# drive_logic.net
KiCad netlist of a schematic drawn in Altium Designer
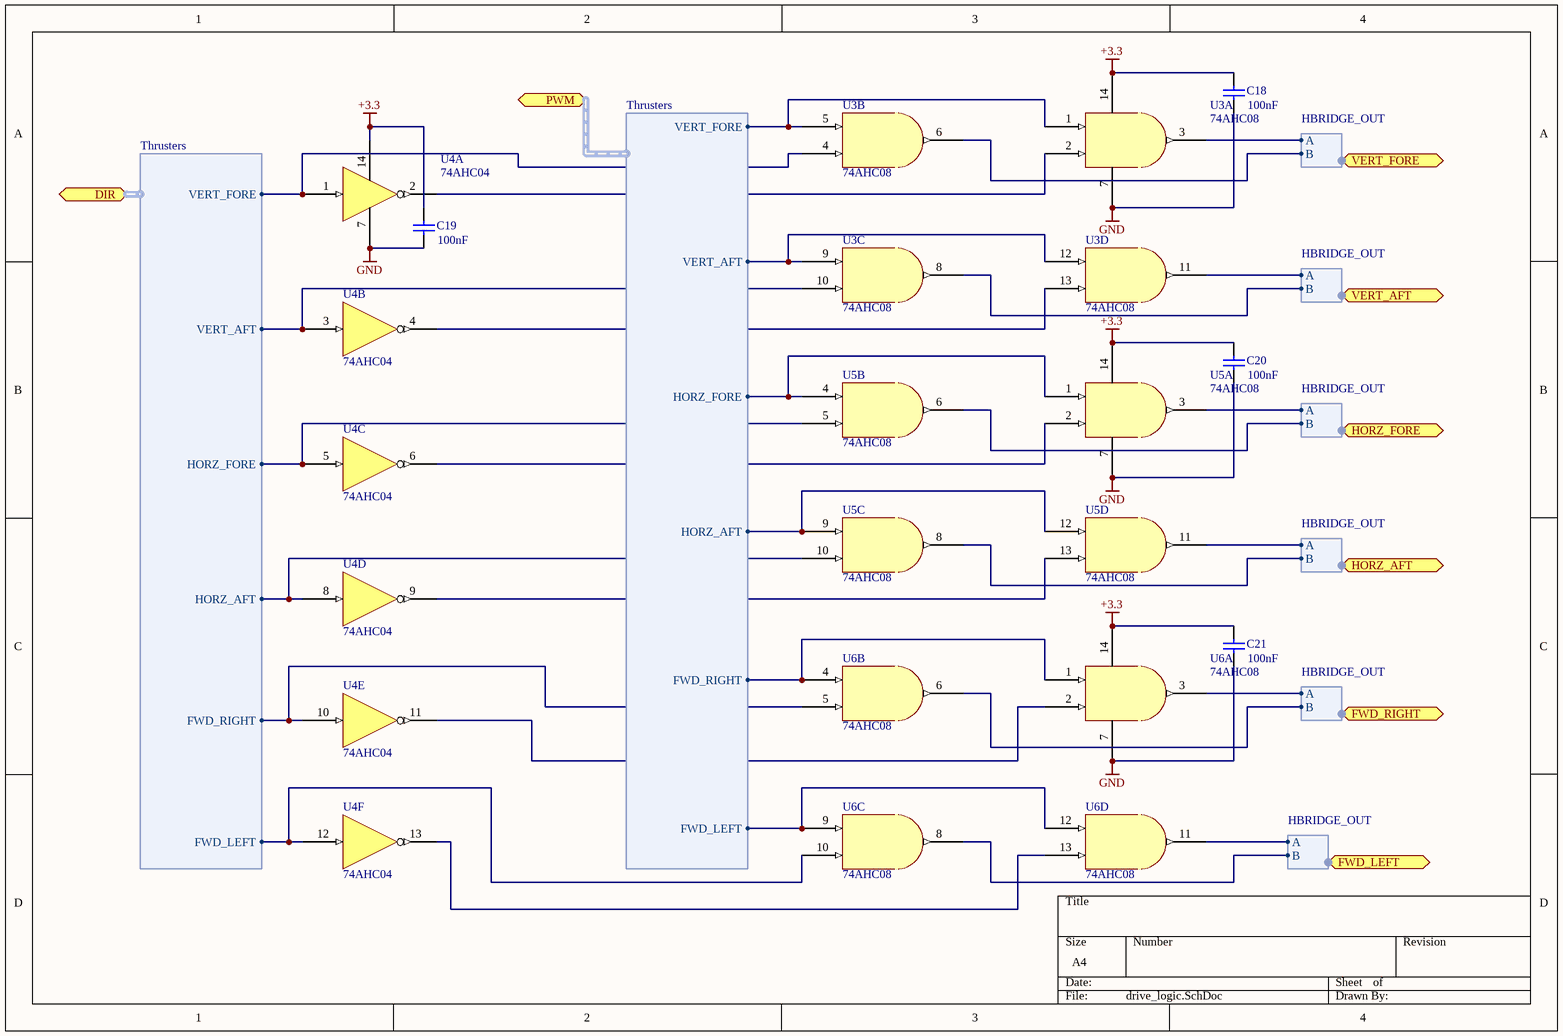
[diagram p0: drive_logic.SchDoc]

(export (version "E")
  (design (tool "Eeschema 10.0.6"))
  (components
    (comp (ref "C18")
      (value "100nF")
      (footprint "C0603")
      (description "Capacitor")
      (fields (field (name "Comment") "Cap") (field (name "PUBLISHER") "Altium Limited"))
      (libsource (lib "Miscellaneous Devices") (part "Cap"))
    )
    (comp (ref "C19")
      (value "100nF")
      (footprint "C0603")
      (description "Capacitor")
      (fields (field (name "Comment") "Cap") (field (name "PUBLISHER") "Altium Limited"))
      (libsource (lib "Miscellaneous Devices") (part "Cap"))
    )
    (comp (ref "C20")
      (value "100nF")
      (footprint "C0603")
      (description "Capacitor")
      (fields (field (name "Comment") "Cap") (field (name "PUBLISHER") "Altium Limited"))
      (libsource (lib "Miscellaneous Devices") (part "Cap"))
    )
    (comp (ref "C21")
      (value "100nF")
      (footprint "C0603")
      (description "Capacitor")
      (fields (field (name "Comment") "Cap") (field (name "PUBLISHER") "Altium Limited"))
      (libsource (lib "Miscellaneous Devices") (part "Cap"))
    )
    (comp (ref "U3")
      (value "74AHC08")
      (description "TTL Quad AND gate")
      (libsource (lib "SN74AHC08") (part "74AHC08"))
    )
    (comp (ref "U4")
      (value "74AHC04")
      (description "TTL Hex inverter")
      (libsource (lib "75ACH04") (part "74AHC04"))
    )
    (comp (ref "U5")
      (value "74AHC08")
      (description "TTL Quad AND gate")
      (libsource (lib "SN74AHC08") (part "74AHC08"))
    )
    (comp (ref "U6")
      (value "74AHC08")
      (description "TTL Quad AND gate")
      (libsource (lib "SN74AHC08") (part "74AHC08"))
    )
  )
  (nets
    (net (code "3") (name "+3.3") (class "Default")
      (node (ref "C18") (pin "2") (pinfunction "2_2") (pintype "passive"))
      (node (ref "C19") (pin "2") (pinfunction "2_2") (pintype "passive"))
      (node (ref "C20") (pin "2") (pinfunction "2_2") (pintype "passive"))
      (node (ref "C21") (pin "2") (pinfunction "2_2") (pintype "passive"))
      (node (ref "U3") (pin "14") (pintype "power_in"))
      (node (ref "U4") (pin "14") (pintype "power_in"))
      (node (ref "U5") (pin "14") (pintype "power_in"))
      (node (ref "U6") (pin "14") (pintype "power_in"))
    )
    (net (code "6") (name "GND") (class "Default")
      (node (ref "C18") (pin "1") (pinfunction "1_1") (pintype "passive"))
      (node (ref "C19") (pin "1") (pinfunction "1_1") (pintype "passive"))
      (node (ref "C20") (pin "1") (pinfunction "1_1") (pintype "passive"))
      (node (ref "C21") (pin "1") (pinfunction "1_1") (pintype "passive"))
      (node (ref "U3") (pin "7") (pintype "power_in"))
      (node (ref "U4") (pin "7") (pintype "power_in"))
      (node (ref "U5") (pin "7") (pintype "power_in"))
      (node (ref "U6") (pin "7") (pintype "power_in"))
    )
    (net (code "7") (name "Net-(U3-Pad1)") (class "Default")
      (node (ref "U3") (pin "1") (pintype "input"))
      (node (ref "U3") (pin "5") (pintype "input"))
    )
    (net (code "8") (name "Net-(U3-Pad2)") (class "Default")
      (node (ref "U3") (pin "2") (pintype "input"))
      (node (ref "U4") (pin "2") (pintype "output"))
    )
    (net (code "9") (name "Net-(U3-Pad4)") (class "Default")
      (node (ref "U3") (pin "4") (pintype "input"))
      (node (ref "U4") (pin "1") (pintype "input"))
    )
    (net (code "10") (name "Net-(U3-Pad10)") (class "Default")
      (node (ref "U3") (pin "10") (pintype "input"))
      (node (ref "U4") (pin "3") (pintype "input"))
    )
    (net (code "11") (name "Net-(U3-Pad12)") (class "Default")
      (node (ref "U3") (pin "12") (pintype "input"))
      (node (ref "U3") (pin "9") (pintype "input"))
    )
    (net (code "12") (name "Net-(U3-Pad13)") (class "Default")
      (node (ref "U3") (pin "13") (pintype "input"))
      (node (ref "U4") (pin "4") (pintype "output"))
    )
    (net (code "13") (name "Net-(U4-Pad5)") (class "Default")
      (node (ref "U4") (pin "5") (pintype "input"))
      (node (ref "U5") (pin "5") (pintype "input"))
    )
    (net (code "14") (name "Net-(U4-Pad6)") (class "Default")
      (node (ref "U4") (pin "6") (pintype "output"))
      (node (ref "U5") (pin "2") (pintype "input"))
    )
    (net (code "15") (name "Net-(U4-Pad8)") (class "Default")
      (node (ref "U4") (pin "8") (pintype "input"))
      (node (ref "U5") (pin "10") (pintype "input"))
    )
    (net (code "16") (name "Net-(U4-Pad9)") (class "Default")
      (node (ref "U4") (pin "9") (pintype "output"))
      (node (ref "U5") (pin "13") (pintype "input"))
    )
    (net (code "17") (name "Net-(U4-Pad10)") (class "Default")
      (node (ref "U4") (pin "10") (pintype "input"))
      (node (ref "U6") (pin "5") (pintype "input"))
    )
    (net (code "18") (name "Net-(U4-Pad11)") (class "Default")
      (node (ref "U4") (pin "11") (pintype "output"))
      (node (ref "U6") (pin "2") (pintype "input"))
    )
    (net (code "19") (name "Net-(U4-Pad12)") (class "Default")
      (node (ref "U4") (pin "12") (pintype "input"))
      (node (ref "U6") (pin "10") (pintype "input"))
    )
    (net (code "20") (name "Net-(U4-Pad13)") (class "Default")
      (node (ref "U4") (pin "13") (pintype "output"))
      (node (ref "U6") (pin "13") (pintype "input"))
    )
    (net (code "21") (name "Net-(U5-Pad1)") (class "Default")
      (node (ref "U5") (pin "1") (pintype "input"))
      (node (ref "U5") (pin "4") (pintype "input"))
    )
    (net (code "22") (name "Net-(U5-Pad12)") (class "Default")
      (node (ref "U5") (pin "12") (pintype "input"))
      (node (ref "U5") (pin "9") (pintype "input"))
    )
    (net (code "23") (name "Net-(U6-Pad1)") (class "Default")
      (node (ref "U6") (pin "1") (pintype "input"))
      (node (ref "U6") (pin "4") (pintype "input"))
    )
    (net (code "24") (name "Net-(U6-Pad12)") (class "Default")
      (node (ref "U6") (pin "12") (pintype "input"))
      (node (ref "U6") (pin "9") (pintype "input"))
    )
    (net (code "25") (name "unconnected-(U3-Pad3)") (class "Default")
      (node (ref "U3") (pin "3") (pintype "output"))
    )
    (net (code "26") (name "unconnected-(U3-Pad6)") (class "Default")
      (node (ref "U3") (pin "6") (pintype "output"))
    )
    (net (code "27") (name "unconnected-(U3-Pad8)") (class "Default")
      (node (ref "U3") (pin "8") (pintype "output"))
    )
    (net (code "28") (name "unconnected-(U3-Pad11)") (class "Default")
      (node (ref "U3") (pin "11") (pintype "output"))
    )
    (net (code "29") (name "unconnected-(U5-Pad3)") (class "Default")
      (node (ref "U5") (pin "3") (pintype "output"))
    )
    (net (code "30") (name "unconnected-(U5-Pad6)") (class "Default")
      (node (ref "U5") (pin "6") (pintype "output"))
    )
    (net (code "31") (name "unconnected-(U5-Pad8)") (class "Default")
      (node (ref "U5") (pin "8") (pintype "output"))
    )
    (net (code "32") (name "unconnected-(U5-Pad11)") (class "Default")
      (node (ref "U5") (pin "11") (pintype "output"))
    )
    (net (code "33") (name "unconnected-(U6-Pad3)") (class "Default")
      (node (ref "U6") (pin "3") (pintype "output"))
    )
    (net (code "34") (name "unconnected-(U6-Pad6)") (class "Default")
      (node (ref "U6") (pin "6") (pintype "output"))
    )
    (net (code "35") (name "unconnected-(U6-Pad8)") (class "Default")
      (node (ref "U6") (pin "8") (pintype "output"))
    )
    (net (code "36") (name "unconnected-(U6-Pad11)") (class "Default")
      (node (ref "U6") (pin "11") (pintype "output"))
    )
  )
)
